# tx.net
KiCad netlist of a schematic drawn in EAGLE
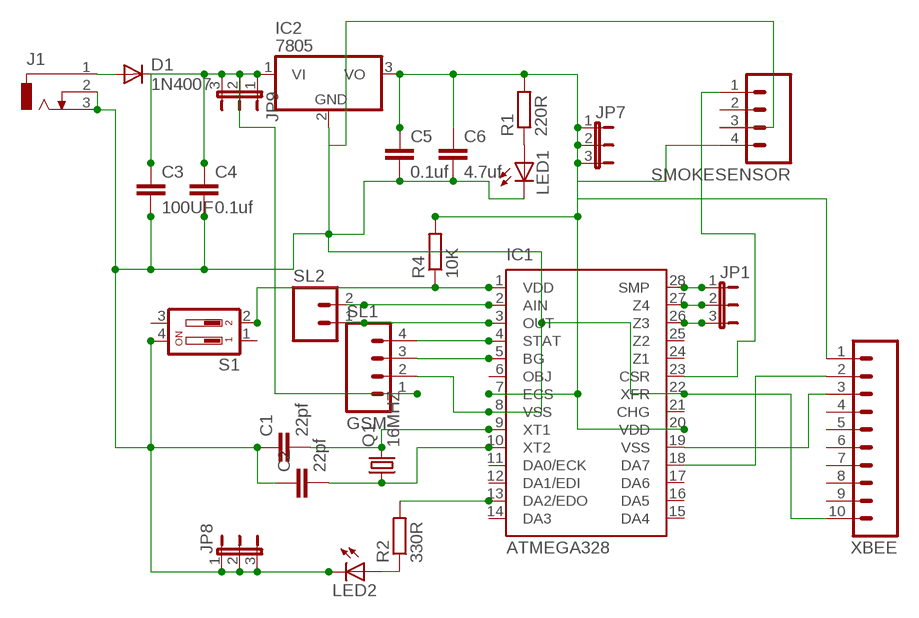
[diagram p0: schematic, sheet 1]

(export (version "E")
  (design (tool "Eeschema 10.0.6"))
  (components
    (comp (ref "C1")
      (value "22pf")
      (footprint "eagle-import:C2.5-2")
      (libsource (lib "eagle-import") (part "C2.5/2"))
    )
    (comp (ref "C2")
      (value "22pf")
      (footprint "eagle-import:C2.5-2")
      (libsource (lib "eagle-import") (part "C2.5/2"))
    )
    (comp (ref "C3")
      (value "100UF")
      (footprint "eagle-import:C2.5-2")
      (libsource (lib "eagle-import") (part "C2.5/2"))
    )
    (comp (ref "C4")
      (value "0.1uf")
      (footprint "eagle-import:C2.5-2")
      (libsource (lib "eagle-import") (part "C2.5/2"))
    )
    (comp (ref "C5")
      (value "0.1uf")
      (footprint "eagle-import:C2.5-2")
      (libsource (lib "eagle-import") (part "C2.5/2"))
    )
    (comp (ref "C6")
      (value "4.7uf")
      (footprint "eagle-import:C2.5-2")
      (libsource (lib "eagle-import") (part "C2.5/2"))
    )
    (comp (ref "D1")
      (value "1N4007")
      (footprint "eagle-import:DO41-10")
      (libsource (lib "eagle-import") (part "1N4004"))
    )
    (comp (ref "IC1")
      (value "ATMEGA328")
      (footprint "eagle-import:DIL28-3")
      (libsource (lib "eagle-import") (part "QT9701BD"))
    )
    (comp (ref "IC2")
      (value "7805")
      (footprint "eagle-import:TO220V")
      (libsource (lib "eagle-import") (part "78TV6"))
    )
    (comp (ref "J1")
      (value "DCJ0303")
      (footprint "eagle-import:DCJ0303")
      (libsource (lib "eagle-import") (part "DCJ0303"))
    )
    (comp (ref "JP1")
      (value "JP2E")
      (footprint "eagle-import:JP2")
      (libsource (lib "eagle-import") (part "JP2E"))
    )
    (comp (ref "JP7")
      (value "JP2E")
      (footprint "eagle-import:JP2")
      (libsource (lib "eagle-import") (part "JP2E"))
    )
    (comp (ref "JP8")
      (value "JP2E")
      (footprint "eagle-import:JP2")
      (libsource (lib "eagle-import") (part "JP2E"))
    )
    (comp (ref "JP9")
      (value "JP2E")
      (footprint "eagle-import:JP2")
      (libsource (lib "eagle-import") (part "JP2E"))
    )
    (comp (ref "LED1")
      (value "LED3MM")
      (footprint "eagle-import:LED3MM")
      (libsource (lib "eagle-import") (part "LED3MM"))
    )
    (comp (ref "LED2")
      (value "LED3MM")
      (footprint "eagle-import:LED3MM")
      (libsource (lib "eagle-import") (part "LED3MM"))
    )
    (comp (ref "Q1")
      (value "16MHZ")
      (footprint "eagle-import:HC49_S")
      (libsource (lib "eagle-import") (part "CRYSTALHC49S"))
    )
    (comp (ref "R1")
      (value "220R")
      (footprint "eagle-import:0207_10")
      (libsource (lib "eagle-import") (part "R-EU_0207/10"))
    )
    (comp (ref "R2")
      (value "330R")
      (footprint "eagle-import:0207_10")
      (libsource (lib "eagle-import") (part "R-EU_0207/10"))
    )
    (comp (ref "R4")
      (value "10K")
      (footprint "eagle-import:0207_10")
      (libsource (lib "eagle-import") (part "R-EU_0207/10"))
    )
    (comp (ref "S1")
      (value "DP02")
      (footprint "eagle-import:DP-02")
      (fields (field (name "MPN") "MCDP02"))
      (libsource (lib "eagle-import") (part "DP02"))
    )
    (comp (ref "SL1")
      (value "GSM")
      (footprint "eagle-import:04P")
      (libsource (lib "eagle-import") (part "M04"))
    )
    (comp (ref "SL2")
      (value "M02")
      (footprint "eagle-import:02P")
      (libsource (lib "eagle-import") (part "M02"))
    )
    (comp (ref "SMOKESENSOR")
      (value "M04")
      (footprint "eagle-import:04P")
      (libsource (lib "eagle-import") (part "M04"))
    )
    (comp (ref "XBEE")
      (value "M10")
      (footprint "eagle-import:10P")
      (libsource (lib "eagle-import") (part "M10"))
    )
  )
  (nets
    (net (code "1") (name "Net-(D1-PadA)") (class "Default")
      (node (ref "D1") (pin "A") (pinfunction "A_A") (pintype "passive"))
      (node (ref "J1") (pin "1") (pinfunction "1_1") (pintype "passive"))
    )
    (net (code "2") (name "Net-(IC1-AIN)") (class "Default")
      (node (ref "IC1") (pin "2") (pinfunction "AIN_2") (pintype "input"))
      (node (ref "SL2") (pin "2") (pinfunction "2_2") (pintype "passive"))
    )
    (net (code "3") (name "Net-(IC1-BG)") (class "Default")
      (node (ref "IC1") (pin "5") (pinfunction "BG_5") (pintype "input"))
      (node (ref "SL1") (pin "3") (pinfunction "3_3") (pintype "passive"))
    )
    (net (code "4") (name "Net-(IC1-CSR)") (class "Default")
      (node (ref "IC1") (pin "23") (pinfunction "CSR_23") (pintype "output"))
      (node (ref "SMOKESENSOR") (pin "1") (pinfunction "1_1") (pintype "passive"))
    )
    (net (code "5") (name "Net-(IC1-DA2{slash}EDO)") (class "Default")
      (node (ref "IC1") (pin "13") (pinfunction "DA2/EDO_13") (pintype "output"))
      (node (ref "R2") (pin "2") (pinfunction "2_2") (pintype "passive"))
    )
    (net (code "6") (name "Net-(IC1-DA7)") (class "Default")
      (node (ref "IC1") (pin "18") (pinfunction "DA7_18") (pintype "output"))
      (node (ref "XBEE") (pin "2") (pinfunction "2_2") (pintype "passive"))
    )
    (net (code "7") (name "Net-(IC1-ECS)") (class "Default")
      (node (ref "C5") (pin "1") (pinfunction "1_1") (pintype "passive"))
      (node (ref "C6") (pin "1") (pinfunction "1_1") (pintype "passive"))
      (node (ref "IC1") (pin "20") (pinfunction "VDD_20") (pintype "input"))
      (node (ref "IC1") (pin "7") (pinfunction "ECS_7") (pintype "output"))
      (node (ref "IC2") (pin "3") (pinfunction "VO_3") (pintype "passive"))
      (node (ref "JP7") (pin "1") (pinfunction "1_1") (pintype "passive"))
      (node (ref "JP7") (pin "2") (pinfunction "2_2") (pintype "passive"))
      (node (ref "JP7") (pin "3") (pinfunction "3_3") (pintype "passive"))
      (node (ref "R1") (pin "2") (pinfunction "2_2") (pintype "passive"))
      (node (ref "R4") (pin "2") (pinfunction "2_2") (pintype "passive"))
      (node (ref "SMOKESENSOR") (pin "4") (pinfunction "4_4") (pintype "passive"))
      (node (ref "XBEE") (pin "1") (pinfunction "1_1") (pintype "passive"))
    )
    (net (code "8") (name "Net-(IC1-OUT)") (class "Default")
      (node (ref "IC1") (pin "3") (pinfunction "OUT_3") (pintype "output"))
      (node (ref "SL2") (pin "1") (pinfunction "1_1") (pintype "passive"))
    )
    (net (code "9") (name "Net-(IC1-SMP)") (class "Default")
      (node (ref "IC1") (pin "28") (pinfunction "SMP_28") (pintype "output"))
      (node (ref "JP1") (pin "1") (pinfunction "1_1") (pintype "passive"))
    )
    (net (code "10") (name "Net-(IC1-STAT)") (class "Default")
      (node (ref "IC1") (pin "4") (pinfunction "STAT_4") (pintype "output"))
      (node (ref "SL1") (pin "4") (pinfunction "4_4") (pintype "passive"))
    )
    (net (code "11") (name "Net-(IC1-VDD-Pad1)") (class "Default")
      (node (ref "IC1") (pin "1") (pinfunction "VDD_1") (pintype "input"))
      (node (ref "R4") (pin "1") (pinfunction "1_1") (pintype "passive"))
      (node (ref "S1") (pin "2") (pinfunction "2_2") (pintype "passive"))
    )
    (net (code "12") (name "Net-(IC1-VSS-Pad19)") (class "Default")
      (node (ref "IC1") (pin "19") (pinfunction "VSS_19") (pintype "input"))
      (node (ref "XBEE") (pin "3") (pinfunction "3_3") (pintype "passive"))
    )
    (net (code "13") (name "Net-(IC1-XFR)") (class "Default")
      (node (ref "C1") (pin "1") (pinfunction "1_1") (pintype "passive"))
      (node (ref "C2") (pin "1") (pinfunction "1_1") (pintype "passive"))
      (node (ref "C3") (pin "2") (pinfunction "2_2") (pintype "passive"))
      (node (ref "C4") (pin "2") (pinfunction "2_2") (pintype "passive"))
      (node (ref "C5") (pin "2") (pinfunction "2_2") (pintype "passive"))
      (node (ref "C6") (pin "2") (pinfunction "2_2") (pintype "passive"))
      (node (ref "IC1") (pin "22") (pinfunction "XFR_22") (pintype "output"))
      (node (ref "IC1") (pin "8") (pinfunction "VSS_8") (pintype "input"))
      (node (ref "IC2") (pin "2") (pinfunction "GND_2") (pintype "passive"))
      (node (ref "J1") (pin "2") (pinfunction "2_2") (pintype "passive"))
      (node (ref "J1") (pin "3") (pinfunction "3_3") (pintype "passive"))
      (node (ref "JP8") (pin "1") (pinfunction "1_1") (pintype "passive"))
      (node (ref "JP8") (pin "2") (pinfunction "2_2") (pintype "passive"))
      (node (ref "JP8") (pin "3") (pinfunction "3_3") (pintype "passive"))
      (node (ref "LED1") (pin "K") (pinfunction "C_K") (pintype "passive"))
      (node (ref "LED2") (pin "K") (pinfunction "C_K") (pintype "passive"))
      (node (ref "S1") (pin "4") (pinfunction "4_4") (pintype "passive"))
      (node (ref "SL1") (pin "2") (pinfunction "2_2") (pintype "passive"))
      (node (ref "SMOKESENSOR") (pin "3") (pinfunction "3_3") (pintype "passive"))
      (node (ref "XBEE") (pin "10") (pinfunction "10_10") (pintype "passive"))
    )
    (net (code "14") (name "Net-(IC1-XT1)") (class "Default")
      (node (ref "C1") (pin "2") (pinfunction "2_2") (pintype "passive"))
      (node (ref "IC1") (pin "9") (pinfunction "XT1_9") (pintype "input"))
      (node (ref "Q1") (pin "2") (pinfunction "2_2") (pintype "passive"))
    )
    (net (code "15") (name "Net-(IC1-XT2)") (class "Default")
      (node (ref "C2") (pin "2") (pinfunction "2_2") (pintype "passive"))
      (node (ref "IC1") (pin "10") (pinfunction "XT2_10") (pintype "output"))
      (node (ref "Q1") (pin "1") (pinfunction "1_1") (pintype "passive"))
    )
    (net (code "16") (name "Net-(IC1-Z3)") (class "Default")
      (node (ref "IC1") (pin "26") (pinfunction "Z3_26") (pintype "output"))
      (node (ref "JP1") (pin "3") (pinfunction "3_3") (pintype "passive"))
    )
    (net (code "17") (name "Net-(IC1-Z4)") (class "Default")
      (node (ref "IC1") (pin "27") (pinfunction "Z4_27") (pintype "output"))
      (node (ref "JP1") (pin "2") (pinfunction "2_2") (pintype "passive"))
    )
    (net (code "18") (name "Net-(IC2-VI)") (class "Default")
      (node (ref "C3") (pin "1") (pinfunction "1_1") (pintype "passive"))
      (node (ref "C4") (pin "1") (pinfunction "1_1") (pintype "passive"))
      (node (ref "D1") (pin "C") (pinfunction "C_C") (pintype "passive"))
      (node (ref "IC2") (pin "1") (pinfunction "VI_1") (pintype "input"))
      (node (ref "JP9") (pin "1") (pinfunction "1_1") (pintype "passive"))
      (node (ref "JP9") (pin "2") (pinfunction "2_2") (pintype "passive"))
      (node (ref "JP9") (pin "3") (pinfunction "3_3") (pintype "passive"))
      (node (ref "SL1") (pin "1") (pinfunction "1_1") (pintype "passive"))
    )
    (net (code "19") (name "Net-(LED1-PadA)") (class "Default")
      (node (ref "LED1") (pin "A") (pinfunction "A_A") (pintype "passive"))
      (node (ref "R1") (pin "1") (pinfunction "1_1") (pintype "passive"))
    )
    (net (code "20") (name "Net-(LED2-PadA)") (class "Default")
      (node (ref "LED2") (pin "A") (pinfunction "A_A") (pintype "passive"))
      (node (ref "R2") (pin "1") (pinfunction "1_1") (pintype "passive"))
    )
    (net (code "21") (name "unconnected-(IC1-CHG-Pad21)") (class "Default")
      (node (ref "IC1") (pin "21") (pinfunction "CHG_21") (pintype "output"))
    )
    (net (code "22") (name "unconnected-(IC1-DA0{slash}ECK-Pad11)") (class "Default")
      (node (ref "IC1") (pin "11") (pinfunction "DA0/ECK_11") (pintype "output"))
    )
    (net (code "23") (name "unconnected-(IC1-DA1{slash}EDI-Pad12)") (class "Default")
      (node (ref "IC1") (pin "12") (pinfunction "DA1/EDI_12") (pintype "output"))
    )
    (net (code "24") (name "unconnected-(IC1-DA3-Pad14)") (class "Default")
      (node (ref "IC1") (pin "14") (pinfunction "DA3_14") (pintype "output"))
    )
    (net (code "25") (name "unconnected-(IC1-DA4-Pad15)") (class "Default")
      (node (ref "IC1") (pin "15") (pinfunction "DA4_15") (pintype "output"))
    )
    (net (code "26") (name "unconnected-(IC1-DA5-Pad16)") (class "Default")
      (node (ref "IC1") (pin "16") (pinfunction "DA5_16") (pintype "output"))
    )
    (net (code "27") (name "unconnected-(IC1-DA6-Pad17)") (class "Default")
      (node (ref "IC1") (pin "17") (pinfunction "DA6_17") (pintype "output"))
    )
    (net (code "28") (name "unconnected-(IC1-OBJ-Pad6)") (class "Default")
      (node (ref "IC1") (pin "6") (pinfunction "OBJ_6") (pintype "input"))
    )
    (net (code "29") (name "unconnected-(IC1-Z1-Pad24)") (class "Default")
      (node (ref "IC1") (pin "24") (pinfunction "Z1_24") (pintype "output"))
    )
    (net (code "30") (name "unconnected-(IC1-Z2-Pad25)") (class "Default")
      (node (ref "IC1") (pin "25") (pinfunction "Z2_25") (pintype "output"))
    )
    (net (code "31") (name "unconnected-(S1-Pad1)") (class "Default")
      (node (ref "S1") (pin "1") (pinfunction "1_1") (pintype "passive"))
    )
    (net (code "32") (name "unconnected-(S1-Pad3)") (class "Default")
      (node (ref "S1") (pin "3") (pinfunction "3_3") (pintype "passive"))
    )
    (net (code "33") (name "unconnected-(SMOKESENSOR-Pad2)") (class "Default")
      (node (ref "SMOKESENSOR") (pin "2") (pinfunction "2_2") (pintype "passive"))
    )
    (net (code "34") (name "unconnected-(XBEE-Pad4)") (class "Default")
      (node (ref "XBEE") (pin "4") (pinfunction "4_4") (pintype "passive"))
    )
    (net (code "35") (name "unconnected-(XBEE-Pad5)") (class "Default")
      (node (ref "XBEE") (pin "5") (pinfunction "5_5") (pintype "passive"))
    )
    (net (code "36") (name "unconnected-(XBEE-Pad6)") (class "Default")
      (node (ref "XBEE") (pin "6") (pinfunction "6_6") (pintype "passive"))
    )
    (net (code "37") (name "unconnected-(XBEE-Pad7)") (class "Default")
      (node (ref "XBEE") (pin "7") (pinfunction "7_7") (pintype "passive"))
    )
    (net (code "38") (name "unconnected-(XBEE-Pad8)") (class "Default")
      (node (ref "XBEE") (pin "8") (pinfunction "8_8") (pintype "passive"))
    )
    (net (code "39") (name "unconnected-(XBEE-Pad9)") (class "Default")
      (node (ref "XBEE") (pin "9") (pinfunction "9_9") (pintype "passive"))
    )
  )
)
